# Vent_Base.net
KiCad netlist of a schematic drawn in EAGLE
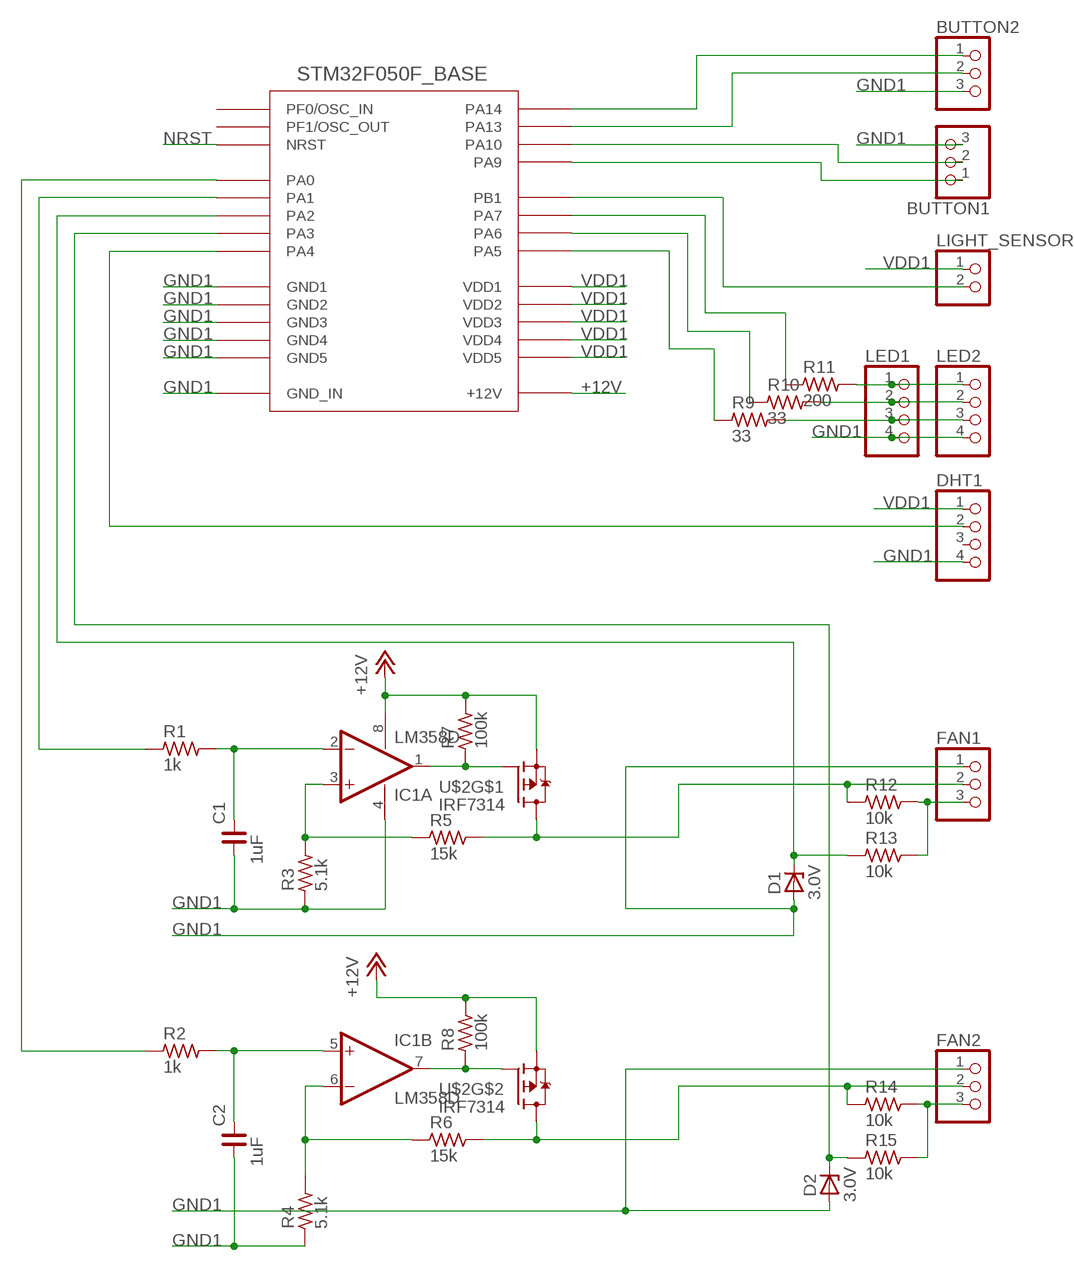
[diagram p0: schematic, sheet 1]

(export (version "E")
  (design (tool "Eeschema 10.0.6"))
  (components
    (comp (ref "BUTTON1")
      (value "PINHD-1X03_2.54-S")
      (footprint "eagle-import:1X03-S")
      (libsource (lib "eagle-import") (part "PINHD-1X03_2.54-S"))
    )
    (comp (ref "BUTTON2")
      (value "PINHD-1X03_2.54-S")
      (footprint "eagle-import:1X03-S")
      (libsource (lib "eagle-import") (part "PINHD-1X03_2.54-S"))
    )
    (comp (ref "C1")
      (value "1uF")
      (footprint "eagle-import:C1206")
      (libsource (lib "eagle-import") (part "C_1206"))
    )
    (comp (ref "C2")
      (value "1uF")
      (footprint "eagle-import:C1206")
      (libsource (lib "eagle-import") (part "C_1206"))
    )
    (comp (ref "D1")
      (value "ZENER-DIODESOT23")
      (footprint "eagle-import:SOT23")
      (fields (field (name "BZX84C3V0") "3.0V"))
      (libsource (lib "eagle-import") (part "ZENER-DIODESOT23"))
    )
    (comp (ref "D2")
      (value "ZENER-DIODESOT23")
      (footprint "eagle-import:SOT23")
      (fields (field (name "BZX84C3V0") "3.0V"))
      (libsource (lib "eagle-import") (part "ZENER-DIODESOT23"))
    )
    (comp (ref "DHT1")
      (value "PINHD-1X04_2.54-S")
      (footprint "eagle-import:1X04-S")
      (libsource (lib "eagle-import") (part "PINHD-1X04_2.54-S"))
    )
    (comp (ref "FAN1")
      (value "PINHD-1X03_2.54-S")
      (footprint "eagle-import:1X03-S")
      (libsource (lib "eagle-import") (part "PINHD-1X03_2.54-S"))
    )
    (comp (ref "FAN2")
      (value "PINHD-1X03_2.54-S")
      (footprint "eagle-import:1X03-S")
      (libsource (lib "eagle-import") (part "PINHD-1X03_2.54-S"))
    )
    (comp (ref "IC1")
      (value "LM358D")
      (footprint "eagle-import:SO08")
      (libsource (lib "eagle-import") (part "LM358D"))
    )
    (comp (ref "LED1")
      (value "PINHD-1X04_2.54-S")
      (footprint "eagle-import:1X04-S")
      (libsource (lib "eagle-import") (part "PINHD-1X04_2.54-S"))
    )
    (comp (ref "LED2")
      (value "PINHD-1X04_2.54-S")
      (footprint "eagle-import:1X04-S")
      (libsource (lib "eagle-import") (part "PINHD-1X04_2.54-S"))
    )
    (comp (ref "LIGHT_SENSOR")
      (value "PINHD-1X02_2.54-S")
      (footprint "eagle-import:1X02-S")
      (libsource (lib "eagle-import") (part "PINHD-1X02_2.54-S"))
    )
    (comp (ref "R1")
      (value "1k")
      (footprint "eagle-import:R1206")
      (libsource (lib "eagle-import") (part "R_1206"))
    )
    (comp (ref "R2")
      (value "1k")
      (footprint "eagle-import:R1206")
      (libsource (lib "eagle-import") (part "R_1206"))
    )
    (comp (ref "R3")
      (value "5.1k")
      (footprint "eagle-import:R1206")
      (libsource (lib "eagle-import") (part "R_1206"))
    )
    (comp (ref "R4")
      (value "5.1k")
      (footprint "eagle-import:R1206")
      (libsource (lib "eagle-import") (part "R_1206"))
    )
    (comp (ref "R5")
      (value "15k")
      (footprint "eagle-import:R1206")
      (libsource (lib "eagle-import") (part "R_1206"))
    )
    (comp (ref "R6")
      (value "15k")
      (footprint "eagle-import:R1206")
      (libsource (lib "eagle-import") (part "R_1206"))
    )
    (comp (ref "R7")
      (value "100k")
      (footprint "eagle-import:R1206")
      (libsource (lib "eagle-import") (part "R_1206"))
    )
    (comp (ref "R8")
      (value "100k")
      (footprint "eagle-import:R1206")
      (libsource (lib "eagle-import") (part "R_1206"))
    )
    (comp (ref "R9")
      (value "33")
      (footprint "eagle-import:R1206")
      (libsource (lib "eagle-import") (part "R_1206"))
    )
    (comp (ref "R10")
      (value "33")
      (footprint "eagle-import:R1206")
      (libsource (lib "eagle-import") (part "R_1206"))
    )
    (comp (ref "R11")
      (value "200")
      (footprint "eagle-import:R1206")
      (libsource (lib "eagle-import") (part "R_1206"))
    )
    (comp (ref "R12")
      (value "10k")
      (footprint "eagle-import:R1206")
      (libsource (lib "eagle-import") (part "R_1206"))
    )
    (comp (ref "R13")
      (value "10k")
      (footprint "eagle-import:R1206")
      (libsource (lib "eagle-import") (part "R_1206"))
    )
    (comp (ref "R14")
      (value "10k")
      (footprint "eagle-import:R1206")
      (libsource (lib "eagle-import") (part "R_1206"))
    )
    (comp (ref "R15")
      (value "10k")
      (footprint "eagle-import:R1206")
      (libsource (lib "eagle-import") (part "R_1206"))
    )
    (comp (ref "U$1")
      (value "STM32F050F_BASE_MOD")
      (footprint "eagle-import:STM32_BASE_MOD")
      (libsource (lib "eagle-import") (part "STM32F050F_BASE_MOD"))
    )
    (comp (ref "U$2")
      (value "IRF7314")
      (footprint "eagle-import:SO-8")
      (libsource (lib "eagle-import") (part "IRF7314"))
    )
  )
  (nets
    (net (code "1") (name "+12V") (class "Default")
      (node (ref "IC1") (pin "8") (pinfunction "V+_8") (pintype "power_in"))
      (node (ref "R7") (pin "2") (pinfunction "2_2") (pintype "passive"))
      (node (ref "R8") (pin "2") (pinfunction "2_2") (pintype "passive"))
      (node (ref "U$1") (pin "+12V") (pinfunction "+12V_+12V") (pintype "passive"))
      (node (ref "U$2") (pin "1") (pinfunction "S_1") (pintype "passive"))
      (node (ref "U$2") (pin "3") (pinfunction "S_3") (pintype "passive"))
    )
    (net (code "2") (name "/GND1") (class "Default")
      (node (ref "BUTTON1") (pin "3") (pinfunction "3_3") (pintype "passive"))
      (node (ref "BUTTON2") (pin "3") (pinfunction "3_3") (pintype "passive"))
      (node (ref "C1") (pin "1") (pinfunction "1_1") (pintype "passive"))
      (node (ref "C2") (pin "1") (pinfunction "1_1") (pintype "passive"))
      (node (ref "D1") (pin "1") (pinfunction "A_1") (pintype "passive"))
      (node (ref "D2") (pin "1") (pinfunction "A_1") (pintype "passive"))
      (node (ref "DHT1") (pin "4") (pinfunction "4_4") (pintype "passive"))
      (node (ref "FAN1") (pin "1") (pinfunction "1_1") (pintype "passive"))
      (node (ref "FAN2") (pin "1") (pinfunction "1_1") (pintype "passive"))
      (node (ref "IC1") (pin "4") (pinfunction "V-_4") (pintype "power_in"))
      (node (ref "LED1") (pin "4") (pinfunction "4_4") (pintype "passive"))
      (node (ref "LED2") (pin "4") (pinfunction "4_4") (pintype "passive"))
      (node (ref "R3") (pin "1") (pinfunction "1_1") (pintype "passive"))
      (node (ref "R4") (pin "1") (pinfunction "1_1") (pintype "passive"))
      (node (ref "U$1") (pin "GND1") (pinfunction "GND1_GND1") (pintype "passive"))
      (node (ref "U$1") (pin "GND2") (pinfunction "GND2_GND2") (pintype "passive"))
      (node (ref "U$1") (pin "GND3") (pinfunction "GND3_GND3") (pintype "passive"))
      (node (ref "U$1") (pin "GND4") (pinfunction "GND4_GND4") (pintype "passive"))
      (node (ref "U$1") (pin "GND5") (pinfunction "GND5_GND5") (pintype "passive"))
      (node (ref "U$1") (pin "GND_IN") (pinfunction "GND_IN_GND_IN") (pintype "passive"))
    )
    (net (code "3") (name "/NRST") (class "Default")
      (node (ref "U$1") (pin "NRST") (pinfunction "NRST_NRST") (pintype "passive"))
    )
    (net (code "4") (name "/VDD1") (class "Default")
      (node (ref "DHT1") (pin "1") (pinfunction "1_1") (pintype "passive"))
      (node (ref "LIGHT_SENSOR") (pin "1") (pinfunction "1_1") (pintype "passive"))
      (node (ref "U$1") (pin "VDD1") (pinfunction "VDD1_VDD1") (pintype "passive"))
      (node (ref "U$1") (pin "VDD2") (pinfunction "VDD2_VDD2") (pintype "passive"))
      (node (ref "U$1") (pin "VDD3") (pinfunction "VDD3_VDD3") (pintype "passive"))
      (node (ref "U$1") (pin "VDD4") (pinfunction "VDD4_VDD4") (pintype "passive"))
      (node (ref "U$1") (pin "VDD5") (pinfunction "VDD5_VDD5") (pintype "passive"))
    )
    (net (code "5") (name "Net-(BUTTON1-Pad1)") (class "Default")
      (node (ref "BUTTON1") (pin "1") (pinfunction "1_1") (pintype "passive"))
      (node (ref "U$1") (pin "PA9") (pinfunction "PA9_PA9") (pintype "passive"))
    )
    (net (code "6") (name "Net-(BUTTON1-Pad2)") (class "Default")
      (node (ref "BUTTON1") (pin "2") (pinfunction "2_2") (pintype "passive"))
      (node (ref "U$1") (pin "PA10") (pinfunction "PA10_PA10") (pintype "passive"))
    )
    (net (code "7") (name "Net-(BUTTON2-Pad1)") (class "Default")
      (node (ref "BUTTON2") (pin "1") (pinfunction "1_1") (pintype "passive"))
      (node (ref "U$1") (pin "PA14") (pinfunction "PA14_PA14") (pintype "passive"))
    )
    (net (code "8") (name "Net-(BUTTON2-Pad2)") (class "Default")
      (node (ref "BUTTON2") (pin "2") (pinfunction "2_2") (pintype "passive"))
      (node (ref "U$1") (pin "PA13") (pinfunction "PA13_PA13") (pintype "passive"))
    )
    (net (code "9") (name "Net-(D1-C)") (class "Default")
      (node (ref "D1") (pin "3") (pinfunction "C_3") (pintype "passive"))
      (node (ref "R13") (pin "1") (pinfunction "1_1") (pintype "passive"))
      (node (ref "U$1") (pin "PA2") (pinfunction "PA2_PA2") (pintype "passive"))
    )
    (net (code "10") (name "Net-(D2-C)") (class "Default")
      (node (ref "D2") (pin "3") (pinfunction "C_3") (pintype "passive"))
      (node (ref "R15") (pin "1") (pinfunction "1_1") (pintype "passive"))
      (node (ref "U$1") (pin "PA3") (pinfunction "PA3_PA3") (pintype "passive"))
    )
    (net (code "11") (name "Net-(DHT1-Pad2)") (class "Default")
      (node (ref "DHT1") (pin "2") (pinfunction "2_2") (pintype "passive"))
      (node (ref "U$1") (pin "PA4") (pinfunction "PA4_PA4") (pintype "passive"))
    )
    (net (code "12") (name "Net-(FAN1-Pad2)") (class "Default")
      (node (ref "FAN1") (pin "2") (pinfunction "2_2") (pintype "passive"))
      (node (ref "R12") (pin "1") (pinfunction "1_1") (pintype "passive"))
      (node (ref "R5") (pin "2") (pinfunction "2_2") (pintype "passive"))
      (node (ref "U$2") (pin "7") (pinfunction "D_7") (pintype "passive"))
      (node (ref "U$2") (pin "8") (pinfunction "D_8") (pintype "passive"))
    )
    (net (code "13") (name "Net-(FAN1-Pad3)") (class "Default")
      (node (ref "FAN1") (pin "3") (pinfunction "3_3") (pintype "passive"))
      (node (ref "R12") (pin "2") (pinfunction "2_2") (pintype "passive"))
      (node (ref "R13") (pin "2") (pinfunction "2_2") (pintype "passive"))
    )
    (net (code "14") (name "Net-(FAN2-Pad2)") (class "Default")
      (node (ref "FAN2") (pin "2") (pinfunction "2_2") (pintype "passive"))
      (node (ref "R14") (pin "1") (pinfunction "1_1") (pintype "passive"))
      (node (ref "R6") (pin "2") (pinfunction "2_2") (pintype "passive"))
      (node (ref "U$2") (pin "5") (pinfunction "D_5") (pintype "passive"))
      (node (ref "U$2") (pin "6") (pinfunction "D_6") (pintype "passive"))
    )
    (net (code "15") (name "Net-(FAN2-Pad3)") (class "Default")
      (node (ref "FAN2") (pin "3") (pinfunction "3_3") (pintype "passive"))
      (node (ref "R14") (pin "2") (pinfunction "2_2") (pintype "passive"))
      (node (ref "R15") (pin "2") (pinfunction "2_2") (pintype "passive"))
    )
    (net (code "16") (name "Net-(IC1A-+IN)") (class "Default")
      (node (ref "IC1") (pin "3") (pinfunction "+IN_3") (pintype "input"))
      (node (ref "R3") (pin "2") (pinfunction "2_2") (pintype "passive"))
      (node (ref "R5") (pin "1") (pinfunction "1_1") (pintype "passive"))
    )
    (net (code "17") (name "Net-(IC1A--IN)") (class "Default")
      (node (ref "C1") (pin "2") (pinfunction "2_2") (pintype "passive"))
      (node (ref "IC1") (pin "2") (pinfunction "-IN_2") (pintype "input"))
      (node (ref "R1") (pin "2") (pinfunction "2_2") (pintype "passive"))
    )
    (net (code "18") (name "Net-(IC1A-OUT)") (class "Default")
      (node (ref "IC1") (pin "1") (pinfunction "OUT_1") (pintype "output"))
      (node (ref "R7") (pin "1") (pinfunction "1_1") (pintype "passive"))
      (node (ref "U$2") (pin "2") (pinfunction "G_2") (pintype "passive"))
    )
    (net (code "19") (name "Net-(IC1B-+IN)") (class "Default")
      (node (ref "C2") (pin "2") (pinfunction "2_2") (pintype "passive"))
      (node (ref "IC1") (pin "5") (pinfunction "+IN_5") (pintype "input"))
      (node (ref "R2") (pin "2") (pinfunction "2_2") (pintype "passive"))
    )
    (net (code "20") (name "Net-(IC1B--IN)") (class "Default")
      (node (ref "IC1") (pin "6") (pinfunction "-IN_6") (pintype "input"))
      (node (ref "R4") (pin "2") (pinfunction "2_2") (pintype "passive"))
      (node (ref "R6") (pin "1") (pinfunction "1_1") (pintype "passive"))
    )
    (net (code "21") (name "Net-(IC1B-OUT)") (class "Default")
      (node (ref "IC1") (pin "7") (pinfunction "OUT_7") (pintype "output"))
      (node (ref "R8") (pin "1") (pinfunction "1_1") (pintype "passive"))
      (node (ref "U$2") (pin "4") (pinfunction "G_4") (pintype "passive"))
    )
    (net (code "22") (name "Net-(LED1-Pad1)") (class "Default")
      (node (ref "LED1") (pin "1") (pinfunction "1_1") (pintype "passive"))
      (node (ref "LED2") (pin "1") (pinfunction "1_1") (pintype "passive"))
      (node (ref "R11") (pin "2") (pinfunction "2_2") (pintype "passive"))
    )
    (net (code "23") (name "Net-(LED1-Pad2)") (class "Default")
      (node (ref "LED1") (pin "2") (pinfunction "2_2") (pintype "passive"))
      (node (ref "LED2") (pin "2") (pinfunction "2_2") (pintype "passive"))
      (node (ref "R10") (pin "2") (pinfunction "2_2") (pintype "passive"))
    )
    (net (code "24") (name "Net-(LED1-Pad3)") (class "Default")
      (node (ref "LED1") (pin "3") (pinfunction "3_3") (pintype "passive"))
      (node (ref "LED2") (pin "3") (pinfunction "3_3") (pintype "passive"))
      (node (ref "R9") (pin "2") (pinfunction "2_2") (pintype "passive"))
    )
    (net (code "25") (name "Net-(LIGHT_SENSOR-Pad2)") (class "Default")
      (node (ref "LIGHT_SENSOR") (pin "2") (pinfunction "2_2") (pintype "passive"))
      (node (ref "U$1") (pin "PB1") (pinfunction "PB1_PB1") (pintype "passive"))
    )
    (net (code "26") (name "Net-(R1-Pad1)") (class "Default")
      (node (ref "R1") (pin "1") (pinfunction "1_1") (pintype "passive"))
      (node (ref "U$1") (pin "PA1") (pinfunction "PA1_PA1") (pintype "passive"))
    )
    (net (code "27") (name "Net-(R2-Pad1)") (class "Default")
      (node (ref "R2") (pin "1") (pinfunction "1_1") (pintype "passive"))
      (node (ref "U$1") (pin "PA0") (pinfunction "PA0_PA0") (pintype "passive"))
    )
    (net (code "28") (name "Net-(R9-Pad1)") (class "Default")
      (node (ref "R9") (pin "1") (pinfunction "1_1") (pintype "passive"))
      (node (ref "U$1") (pin "PA5") (pinfunction "PA5_PA5") (pintype "passive"))
    )
    (net (code "29") (name "Net-(R10-Pad1)") (class "Default")
      (node (ref "R10") (pin "1") (pinfunction "1_1") (pintype "passive"))
      (node (ref "U$1") (pin "PA6") (pinfunction "PA6_PA6") (pintype "passive"))
    )
    (net (code "30") (name "Net-(R11-Pad1)") (class "Default")
      (node (ref "R11") (pin "1") (pinfunction "1_1") (pintype "passive"))
      (node (ref "U$1") (pin "PA7") (pinfunction "PA7_PA7") (pintype "passive"))
    )
    (net (code "31") (name "unconnected-(DHT1-Pad3)") (class "Default")
      (node (ref "DHT1") (pin "3") (pinfunction "3_3") (pintype "passive"))
    )
    (net (code "32") (name "unconnected-(U$1-PF0{slash}OSC_IN-PadPF0)") (class "Default")
      (node (ref "U$1") (pin "PF0") (pinfunction "PF0/OSC_IN_PF0") (pintype "passive"))
    )
    (net (code "33") (name "unconnected-(U$1-PF1{slash}OSC_OUT-PadPF1)") (class "Default")
      (node (ref "U$1") (pin "PF1") (pinfunction "PF1/OSC_OUT_PF1") (pintype "passive"))
    )
  )
)
